# DIGITAL_INPUTS.net
KiCad netlist of a schematic drawn in Altium Designer
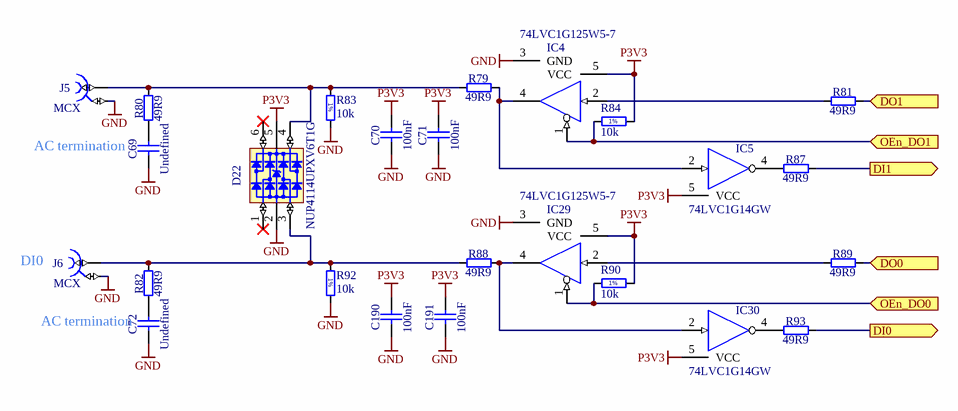
[diagram p0: DIGITAL_INPUTS.SchDoc]

(export (version "E")
  (design (tool "Eeschema 10.0.6"))
  (components
    (comp (ref "C69")
      (value "Undefined")
      (footprint "CAPC1608X90N")
      (description "Non-polarised capacitor")
      (fields (field (name "PART NUMBER") "CC0603_NO-VALUE") (field (name "AUTHOR") "CERN DEM MR"))
      (libsource (lib "Capacitors") (part "Capacitor - non polarized"))
    )
    (comp (ref "C70")
      (value "100nF")
      (footprint "CAPC1005X55N")
      (description "Non-polarised capacitor")
      (fields
        (field (name "PART NUMBER") "CC0402_100NF_16V_10%_X7R")
        (field (name "VOLTAGE") "16V")
        (field (name "AUTHOR") "CERN DEM JLC")
      )
      (libsource (lib "Capacitors") (part "Capacitor - non polarized"))
    )
    (comp (ref "C71")
      (value "100nF")
      (footprint "CAPC1005X55N")
      (description "Non-polarised capacitor")
      (fields
        (field (name "PART NUMBER") "CC0402_100NF_16V_10%_X7R")
        (field (name "VOLTAGE") "16V")
        (field (name "AUTHOR") "CERN DEM JLC")
      )
      (libsource (lib "Capacitors") (part "Capacitor - non polarized"))
    )
    (comp (ref "C72")
      (value "Undefined")
      (footprint "CAPC1608X90N")
      (description "Non-polarised capacitor")
      (fields (field (name "PART NUMBER") "CC0603_NO-VALUE") (field (name "AUTHOR") "CERN DEM MR"))
      (libsource (lib "Capacitors") (part "Capacitor - non polarized"))
    )
    (comp (ref "C190")
      (value "100nF")
      (footprint "CAPC1005X55N")
      (description "Non-polarised capacitor")
      (fields
        (field (name "PART NUMBER") "CC0402_100NF_16V_10%_X7R")
        (field (name "VOLTAGE") "16V")
        (field (name "AUTHOR") "CERN DEM JLC")
      )
      (libsource (lib "Capacitors") (part "Capacitor - non polarized"))
    )
    (comp (ref "C191")
      (value "100nF")
      (footprint "CAPC1005X55N")
      (description "Non-polarised capacitor")
      (fields
        (field (name "PART NUMBER") "CC0402_100NF_16V_10%_X7R")
        (field (name "VOLTAGE") "16V")
        (field (name "AUTHOR") "CERN DEM JLC")
      )
      (libsource (lib "Capacitors") (part "Capacitor - non polarized"))
    )
    (comp (ref "D22")
      (value "NUP4114UPXV6T1G")
      (footprint "SOTFL50P160X60-6N")
      (fields
        (field (name "VOLTAGE") "5.5V")
        (field (name "MANUFACTURER") "ON SEMICONDUCTOR")
        (field (name "AUTHOR") "CERN DEM JLC")
      )
      (libsource (lib "ICs And Semiconductors") (part "NUP4114"))
    )
    (comp (ref "IC4")
      (value "74LVC1G125W5-7")
      (footprint "SOT95P280X145-5N")
      (description "Single Bus Buffer Gate With 3-State Output")
      (fields (field (name "MANUFACTURER") "DIODES") (field (name "AUTHOR") "GK"))
      (libsource (lib "ICS-logic") (part "74LVC1G125W5-7"))
    )
    (comp (ref "IC5")
      (value "74LVC1G14GW")
      (footprint "SOT65P212X110-5N")
      (description "Single Schmitt-Trigger Inverter")
      (fields (field (name "MANUFACTURER") "NXP SEMICONDUCTORS") (field (name "AUTHOR") "CERN DEM JLC"))
      (libsource (lib "ICs And Semiconductors") (part "741G14"))
    )
    (comp (ref "IC29")
      (value "74LVC1G125W5-7")
      (footprint "SOT95P280X145-5N")
      (description "Single Bus Buffer Gate With 3-State Output")
      (fields (field (name "MANUFACTURER") "DIODES") (field (name "AUTHOR") "GK"))
      (libsource (lib "ICS-logic") (part "74LVC1G125W5-7"))
    )
    (comp (ref "IC30")
      (value "74LVC1G14GW")
      (footprint "SOT65P212X110-5N")
      (description "Single Schmitt-Trigger Inverter")
      (fields (field (name "MANUFACTURER") "NXP SEMICONDUCTORS") (field (name "AUTHOR") "CERN DEM JLC"))
      (libsource (lib "ICs And Semiconductors") (part "741G14"))
    )
    (comp (ref "J5")
      (value "MCX")
      (footprint "AMPHENOL_919-383J-51A")
      (fields
        (field (name "PART NUMBER") "AMPHENOL_919-383J-51A")
        (field (name "MANUFACTURER") "AMPHENOL")
        (field (name "MANUFACTURER PART NUMBER") "919-383J-51A")
        (field (name "AUTHOR") "CERN DEM BC")
      )
      (libsource (lib "Connectors") (part "Coax_1Female_1Shield"))
    )
    (comp (ref "J6")
      (value "MCX")
      (footprint "AMPHENOL_919-383J-51A")
      (fields
        (field (name "PART NUMBER") "AMPHENOL_919-383J-51A")
        (field (name "MANUFACTURER") "AMPHENOL")
        (field (name "MANUFACTURER PART NUMBER") "919-383J-51A")
        (field (name "AUTHOR") "CERN DEM BC")
      )
      (libsource (lib "Connectors") (part "Coax_1Female_1Shield"))
    )
    (comp (ref "R79")
      (value "49R9")
      (footprint "RESC1005X40N")
      (description "Resistor - 1%")
      (fields
        (field (name "PART NUMBER") "R0402_49R9_1%_0.0625W_100PPM")
        (field (name "POWER") "0.0625W")
        (field (name "AUTHOR") "CERN DEM JLC")
      )
      (libsource (lib "Resistors") (part "Resistor - 1%"))
    )
    (comp (ref "R80")
      (value "49R9")
      (footprint "RESC1005X40N")
      (description "Resistor - 1%")
      (fields
        (field (name "PART NUMBER") "R0402_49R9_1%_0.0625W_100PPM")
        (field (name "POWER") "0.0625W")
        (field (name "AUTHOR") "CERN DEM JLC")
      )
      (libsource (lib "Resistors") (part "Resistor - 1%"))
    )
    (comp (ref "R81")
      (value "49R9")
      (footprint "RESC1005X40N")
      (description "Resistor - 1%")
      (fields
        (field (name "PART NUMBER") "R0402_49R9_1%_0.0625W_100PPM")
        (field (name "POWER") "0.0625W")
        (field (name "AUTHOR") "CERN DEM JLC")
      )
      (libsource (lib "Resistors") (part "Resistor - 1%"))
    )
    (comp (ref "R82")
      (value "49R9")
      (footprint "RESC1005X40N")
      (description "Resistor - 1%")
      (fields
        (field (name "PART NUMBER") "R0402_49R9_1%_0.0625W_100PPM")
        (field (name "POWER") "0.0625W")
        (field (name "AUTHOR") "CERN DEM JLC")
      )
      (libsource (lib "Resistors") (part "Resistor - 1%"))
    )
    (comp (ref "R83")
      (value "10k")
      (footprint "RESC1005X40N")
      (description "Resistor - 1%")
      (fields
        (field (name "PART NUMBER") "R0402_10K_1%_0.0625W_100PPM")
        (field (name "POWER") "0.0625W")
        (field (name "AUTHOR") "CERN DEM JLC")
      )
      (libsource (lib "Resistors") (part "Resistor - 1%"))
    )
    (comp (ref "R84")
      (value "10k")
      (footprint "RESC1005X40N")
      (description "Resistor - 1%")
      (fields
        (field (name "PART NUMBER") "R0402_10K_1%_0.0625W_100PPM")
        (field (name "POWER") "0.0625W")
        (field (name "AUTHOR") "CERN DEM JLC")
      )
      (libsource (lib "Resistors") (part "Resistor - 1%"))
    )
    (comp (ref "R87")
      (value "49R9")
      (footprint "RESC1005X40N")
      (description "Resistor - 1%")
      (fields
        (field (name "PART NUMBER") "R0402_49R9_1%_0.0625W_100PPM")
        (field (name "POWER") "0.0625W")
        (field (name "AUTHOR") "CERN DEM JLC")
      )
      (libsource (lib "Resistors") (part "Resistor - 1%"))
    )
    (comp (ref "R88")
      (value "49R9")
      (footprint "RESC1005X40N")
      (description "Resistor - 1%")
      (fields
        (field (name "PART NUMBER") "R0402_49R9_1%_0.0625W_100PPM")
        (field (name "POWER") "0.0625W")
        (field (name "AUTHOR") "CERN DEM JLC")
      )
      (libsource (lib "Resistors") (part "Resistor - 1%"))
    )
    (comp (ref "R89")
      (value "49R9")
      (footprint "RESC1005X40N")
      (description "Resistor - 1%")
      (fields
        (field (name "PART NUMBER") "R0402_49R9_1%_0.0625W_100PPM")
        (field (name "POWER") "0.0625W")
        (field (name "AUTHOR") "CERN DEM JLC")
      )
      (libsource (lib "Resistors") (part "Resistor - 1%"))
    )
    (comp (ref "R90")
      (value "10k")
      (footprint "RESC1005X40N")
      (description "Resistor - 1%")
      (fields
        (field (name "PART NUMBER") "R0402_10K_1%_0.0625W_100PPM")
        (field (name "POWER") "0.0625W")
        (field (name "AUTHOR") "CERN DEM JLC")
      )
      (libsource (lib "Resistors") (part "Resistor - 1%"))
    )
    (comp (ref "R92")
      (value "10k")
      (footprint "RESC1005X40N")
      (description "Resistor - 1%")
      (fields
        (field (name "PART NUMBER") "R0402_10K_1%_0.0625W_100PPM")
        (field (name "POWER") "0.0625W")
        (field (name "AUTHOR") "CERN DEM JLC")
      )
      (libsource (lib "Resistors") (part "Resistor - 1%"))
    )
    (comp (ref "R93")
      (value "49R9")
      (footprint "RESC1005X40N")
      (description "Resistor - 1%")
      (fields
        (field (name "PART NUMBER") "R0402_49R9_1%_0.0625W_100PPM")
        (field (name "POWER") "0.0625W")
        (field (name "AUTHOR") "CERN DEM JLC")
      )
      (libsource (lib "Resistors") (part "Resistor - 1%"))
    )
  )
  (nets
    (net (code "1") (name "/DI0") (class "Default")
      (node (ref "R93") (pin "2") (pinfunction "2_2") (pintype "passive"))
    )
    (net (code "2") (name "/DI1") (class "Default")
      (node (ref "R87") (pin "2") (pinfunction "2_2") (pintype "passive"))
    )
    (net (code "3") (name "/DO0") (class "Default")
      (node (ref "R89") (pin "2") (pinfunction "2_2") (pintype "passive"))
    )
    (net (code "4") (name "/DO1") (class "Default")
      (node (ref "R81") (pin "2") (pinfunction "2_2") (pintype "passive"))
    )
    (net (code "5") (name "/OEn_DO0") (class "Default")
      (node (ref "IC29") (pin "1") (pinfunction "~{G}_1") (pintype "input"))
      (node (ref "R90") (pin "1") (pinfunction "1_1") (pintype "passive"))
    )
    (net (code "6") (name "/OEn_DO1") (class "Default")
      (node (ref "IC4") (pin "1") (pinfunction "~{G}_1") (pintype "input"))
      (node (ref "R84") (pin "1") (pinfunction "1_1") (pintype "passive"))
    )
    (net (code "7") (name "GND") (class "Default")
      (node (ref "C190") (pin "1") (pinfunction "1_1") (pintype "passive"))
      (node (ref "C191") (pin "1") (pinfunction "1_1") (pintype "passive"))
      (node (ref "C69") (pin "1") (pinfunction "1_1") (pintype "passive"))
      (node (ref "C70") (pin "1") (pinfunction "1_1") (pintype "passive"))
      (node (ref "C71") (pin "1") (pinfunction "1_1") (pintype "passive"))
      (node (ref "C72") (pin "1") (pinfunction "1_1") (pintype "passive"))
      (node (ref "D22") (pin "2") (pinfunction "GND_2") (pintype "power_in"))
      (node (ref "IC29") (pin "3") (pinfunction "GND_3") (pintype "power_in"))
      (node (ref "IC30") (pin "3") (pinfunction "GND_3") (pintype "power_in"))
      (node (ref "IC4") (pin "3") (pinfunction "GND_3") (pintype "power_in"))
      (node (ref "IC5") (pin "3") (pinfunction "GND_3") (pintype "power_in"))
      (node (ref "J5") (pin "2") (pinfunction "2_2") (pintype "bidirectional"))
      (node (ref "J6") (pin "2") (pinfunction "2_2") (pintype "bidirectional"))
      (node (ref "R83") (pin "2") (pinfunction "2_2") (pintype "passive"))
      (node (ref "R92") (pin "2") (pinfunction "2_2") (pintype "passive"))
    )
    (net (code "8") (name "Net-(C69-Pad2)") (class "Default")
      (node (ref "C69") (pin "2") (pinfunction "2_2") (pintype "passive"))
      (node (ref "R80") (pin "1") (pinfunction "1_1") (pintype "passive"))
    )
    (net (code "9") (name "Net-(C72-Pad2)") (class "Default")
      (node (ref "C72") (pin "2") (pinfunction "2_2") (pintype "passive"))
      (node (ref "R82") (pin "1") (pinfunction "1_1") (pintype "passive"))
    )
    (net (code "10") (name "Net-(D22-I{slash}O2)") (class "Default")
      (node (ref "D22") (pin "3") (pinfunction "I/O2_3") (pintype "bidirectional"))
      (node (ref "J6") (pin "1") (pinfunction "1_1") (pintype "bidirectional"))
      (node (ref "R82") (pin "2") (pinfunction "2_2") (pintype "passive"))
      (node (ref "R88") (pin "1") (pinfunction "1_1") (pintype "passive"))
      (node (ref "R92") (pin "1") (pinfunction "1_1") (pintype "passive"))
    )
    (net (code "11") (name "Net-(D22-I{slash}O3)") (class "Default")
      (node (ref "D22") (pin "4") (pinfunction "I/O3_4") (pintype "bidirectional"))
      (node (ref "J5") (pin "1") (pinfunction "1_1") (pintype "bidirectional"))
      (node (ref "R79") (pin "1") (pinfunction "1_1") (pintype "passive"))
      (node (ref "R80") (pin "2") (pinfunction "2_2") (pintype "passive"))
      (node (ref "R83") (pin "1") (pinfunction "1_1") (pintype "passive"))
    )
    (net (code "12") (name "Net-(IC4-IN)") (class "Default")
      (node (ref "IC4") (pin "2") (pinfunction "IN_2") (pintype "input"))
      (node (ref "R81") (pin "1") (pinfunction "1_1") (pintype "passive"))
    )
    (net (code "13") (name "Net-(IC4-OUT)") (class "Default")
      (node (ref "IC4") (pin "4") (pinfunction "OUT_4") (pintype "tri_state"))
      (node (ref "IC5") (pin "2") (pinfunction "IN_2") (pintype "input"))
      (node (ref "R79") (pin "2") (pinfunction "2_2") (pintype "passive"))
    )
    (net (code "14") (name "Net-(IC5-OUT)") (class "Default")
      (node (ref "IC5") (pin "4") (pinfunction "OUT_4") (pintype "open_collector"))
      (node (ref "R87") (pin "1") (pinfunction "1_1") (pintype "passive"))
    )
    (net (code "15") (name "Net-(IC29-IN)") (class "Default")
      (node (ref "IC29") (pin "2") (pinfunction "IN_2") (pintype "input"))
      (node (ref "R89") (pin "1") (pinfunction "1_1") (pintype "passive"))
    )
    (net (code "16") (name "Net-(IC29-OUT)") (class "Default")
      (node (ref "IC29") (pin "4") (pinfunction "OUT_4") (pintype "tri_state"))
      (node (ref "IC30") (pin "2") (pinfunction "IN_2") (pintype "input"))
      (node (ref "R88") (pin "2") (pinfunction "2_2") (pintype "passive"))
    )
    (net (code "17") (name "Net-(IC30-OUT)") (class "Default")
      (node (ref "IC30") (pin "4") (pinfunction "OUT_4") (pintype "open_collector"))
      (node (ref "R93") (pin "1") (pinfunction "1_1") (pintype "passive"))
    )
    (net (code "18") (name "P3V3") (class "Default")
      (node (ref "C190") (pin "2") (pinfunction "2_2") (pintype "passive"))
      (node (ref "C191") (pin "2") (pinfunction "2_2") (pintype "passive"))
      (node (ref "C70") (pin "2") (pinfunction "2_2") (pintype "passive"))
      (node (ref "C71") (pin "2") (pinfunction "2_2") (pintype "passive"))
      (node (ref "D22") (pin "5") (pinfunction "VBUS_5") (pintype "power_in"))
      (node (ref "IC29") (pin "5") (pinfunction "VCC_5") (pintype "power_in"))
      (node (ref "IC30") (pin "5") (pinfunction "VCC_5") (pintype "power_in"))
      (node (ref "IC4") (pin "5") (pinfunction "VCC_5") (pintype "power_in"))
      (node (ref "IC5") (pin "5") (pinfunction "VCC_5") (pintype "power_in"))
      (node (ref "R84") (pin "2") (pinfunction "2_2") (pintype "passive"))
      (node (ref "R90") (pin "2") (pinfunction "2_2") (pintype "passive"))
    )
    (net (code "19") (name "unconnected-(D22-I{slash}O1-Pad1)") (class "Default")
      (node (ref "D22") (pin "1") (pinfunction "I/O1_1") (pintype "bidirectional+no_connect"))
    )
    (net (code "20") (name "unconnected-(D22-I{slash}O4-Pad6)") (class "Default")
      (node (ref "D22") (pin "6") (pinfunction "I/O4_6") (pintype "bidirectional+no_connect"))
    )
  )
)
